# workshop.net
KiCad netlist of a schematic drawn in EAGLE
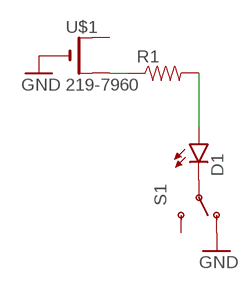
[diagram p0: schematic, sheet 1]

(export (version "E")
  (design (tool "Eeschema 10.0.6"))
  (components
    (comp (ref "D1")
      (value "LED10MM")
      (footprint "eagle-import:LED10MM")
      (libsource (lib "eagle-import") (part "LED10MM"))
    )
    (comp (ref "R1")
      (value "RESISTORKIT")
      (footprint "eagle-import:AXIAL-0.3-KIT")
      (libsource (lib "eagle-import") (part "RESISTORKIT"))
    )
    (comp (ref "S1")
      (value "SWITCH-SPDT-1")
      (footprint "eagle-import:MHS122-1")
      (libsource (lib "eagle-import") (part "SWITCH-SPDT-1"))
    )
    (comp (ref "U$1")
      (value "219-7960")
      (footprint "eagle-import:CR2032-THRU")
      (libsource (lib "eagle-import") (part "CR2032THM"))
    )
  )
  (nets
    (net (code "1") (name "GND") (class "Default")
      (node (ref "S1") (pin "1") (pinfunction "O_1") (pintype "passive"))
      (node (ref "U$1") (pin "-") (pinfunction "-_-") (pintype "passive"))
    )
    (net (code "2") (name "Net-(R1-1)") (class "Default")
      (node (ref "R1") (pin "P$1") (pinfunction "1_P$1") (pintype "passive"))
      (node (ref "U$1") (pin "+2") (pinfunction "+1_+2") (pintype "passive"))
    )
    (net (code "3") (name "Net-(R1-2)") (class "Default")
      (node (ref "D1") (pin "A") (pinfunction "A_A") (pintype "passive"))
      (node (ref "R1") (pin "P$2") (pinfunction "2_P$2") (pintype "passive"))
    )
    (net (code "4") (name "Net-(S1-P)") (class "Default")
      (node (ref "D1") (pin "C") (pinfunction "C_C") (pintype "passive"))
      (node (ref "S1") (pin "2") (pinfunction "P_2") (pintype "passive"))
    )
    (net (code "5") (name "unconnected-(S1-S-Pad3)") (class "Default")
      (node (ref "S1") (pin "3") (pinfunction "S_3") (pintype "passive"))
    )
    (net (code "6") (name "unconnected-(U$1-+-Pad+1)") (class "Default")
      (node (ref "U$1") (pin "+1") (pinfunction "+_+1") (pintype "passive"))
    )
  )
)
